# untitled.net
KiCad netlist of a schematic drawn in EAGLE
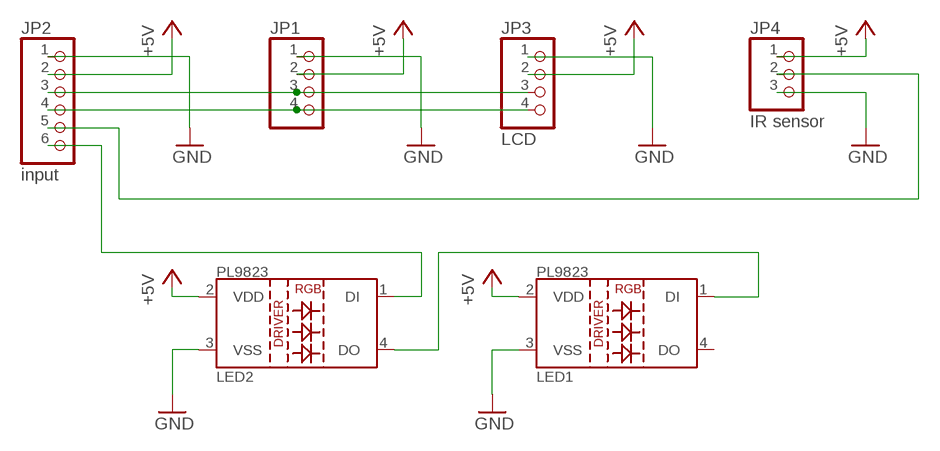
[diagram p0: schematic, sheet 1]

(export (version "E")
  (design (tool "Eeschema 10.0.6"))
  (components
    (comp (ref "JP1")
      (value "PINHD-1X4")
      (footprint "eagle-import:1X04")
      (libsource (lib "eagle-import") (part "PINHD-1X4"))
    )
    (comp (ref "JP2")
      (value "input")
      (footprint "eagle-import:1X06")
      (libsource (lib "eagle-import") (part "PINHD-1X6"))
    )
    (comp (ref "JP3")
      (value "LCD")
      (footprint "eagle-import:1X04")
      (libsource (lib "eagle-import") (part "PINHD-1X4"))
    )
    (comp (ref "JP4")
      (value "IR sensor")
      (footprint "eagle-import:1X03")
      (libsource (lib "eagle-import") (part "PINHD-1X3"))
    )
    (comp (ref "LED1")
      (value "LED-PL9823-F5")
      (footprint "eagle-import:LED-PL9823-F5")
      (libsource (lib "eagle-import") (part "LED-PL9823-F5"))
    )
    (comp (ref "LED2")
      (value "LED-PL9823-F5")
      (footprint "eagle-import:LED-PL9823-F5")
      (libsource (lib "eagle-import") (part "LED-PL9823-F5"))
    )
  )
  (nets
    (net (code "1") (name "+5V") (class "Default")
      (node (ref "JP1") (pin "2") (pinfunction "2_2") (pintype "passive"))
      (node (ref "JP2") (pin "2") (pinfunction "2_2") (pintype "passive"))
      (node (ref "JP3") (pin "2") (pinfunction "2_2") (pintype "passive"))
      (node (ref "JP4") (pin "1") (pinfunction "1_1") (pintype "passive"))
      (node (ref "LED1") (pin "2") (pinfunction "VDD_2") (pintype "bidirectional"))
      (node (ref "LED2") (pin "2") (pinfunction "VDD_2") (pintype "bidirectional"))
    )
    (net (code "2") (name "GND") (class "Default")
      (node (ref "JP1") (pin "1") (pinfunction "1_1") (pintype "passive"))
      (node (ref "JP2") (pin "1") (pinfunction "1_1") (pintype "passive"))
      (node (ref "JP3") (pin "1") (pinfunction "1_1") (pintype "passive"))
      (node (ref "JP4") (pin "3") (pinfunction "3_3") (pintype "passive"))
      (node (ref "LED1") (pin "3") (pinfunction "VSS_3") (pintype "bidirectional"))
      (node (ref "LED2") (pin "3") (pinfunction "VSS_3") (pintype "bidirectional"))
    )
    (net (code "3") (name "Net-(JP1-Pad3)") (class "Default")
      (node (ref "JP1") (pin "3") (pinfunction "3_3") (pintype "passive"))
      (node (ref "JP2") (pin "3") (pinfunction "3_3") (pintype "passive"))
      (node (ref "JP3") (pin "3") (pinfunction "3_3") (pintype "passive"))
    )
    (net (code "4") (name "Net-(JP1-Pad4)") (class "Default")
      (node (ref "JP1") (pin "4") (pinfunction "4_4") (pintype "passive"))
      (node (ref "JP2") (pin "4") (pinfunction "4_4") (pintype "passive"))
      (node (ref "JP3") (pin "4") (pinfunction "4_4") (pintype "passive"))
    )
    (net (code "5") (name "Net-(JP2-Pad5)") (class "Default")
      (node (ref "JP2") (pin "5") (pinfunction "5_5") (pintype "passive"))
      (node (ref "JP4") (pin "2") (pinfunction "2_2") (pintype "passive"))
    )
    (net (code "6") (name "Net-(LED1-DI)") (class "Default")
      (node (ref "LED1") (pin "1") (pinfunction "DI_1") (pintype "bidirectional"))
      (node (ref "LED2") (pin "4") (pinfunction "DO_4") (pintype "bidirectional"))
    )
    (net (code "7") (name "Net-(LED2-DI)") (class "Default")
      (node (ref "JP2") (pin "6") (pinfunction "6_6") (pintype "passive"))
      (node (ref "LED2") (pin "1") (pinfunction "DI_1") (pintype "bidirectional"))
    )
    (net (code "8") (name "unconnected-(LED1-DO-Pad4)") (class "Default")
      (node (ref "LED1") (pin "4") (pinfunction "DO_4") (pintype "bidirectional"))
    )
  )
)
